# sensore-linea.net
KiCad netlist of a schematic drawn in EAGLE
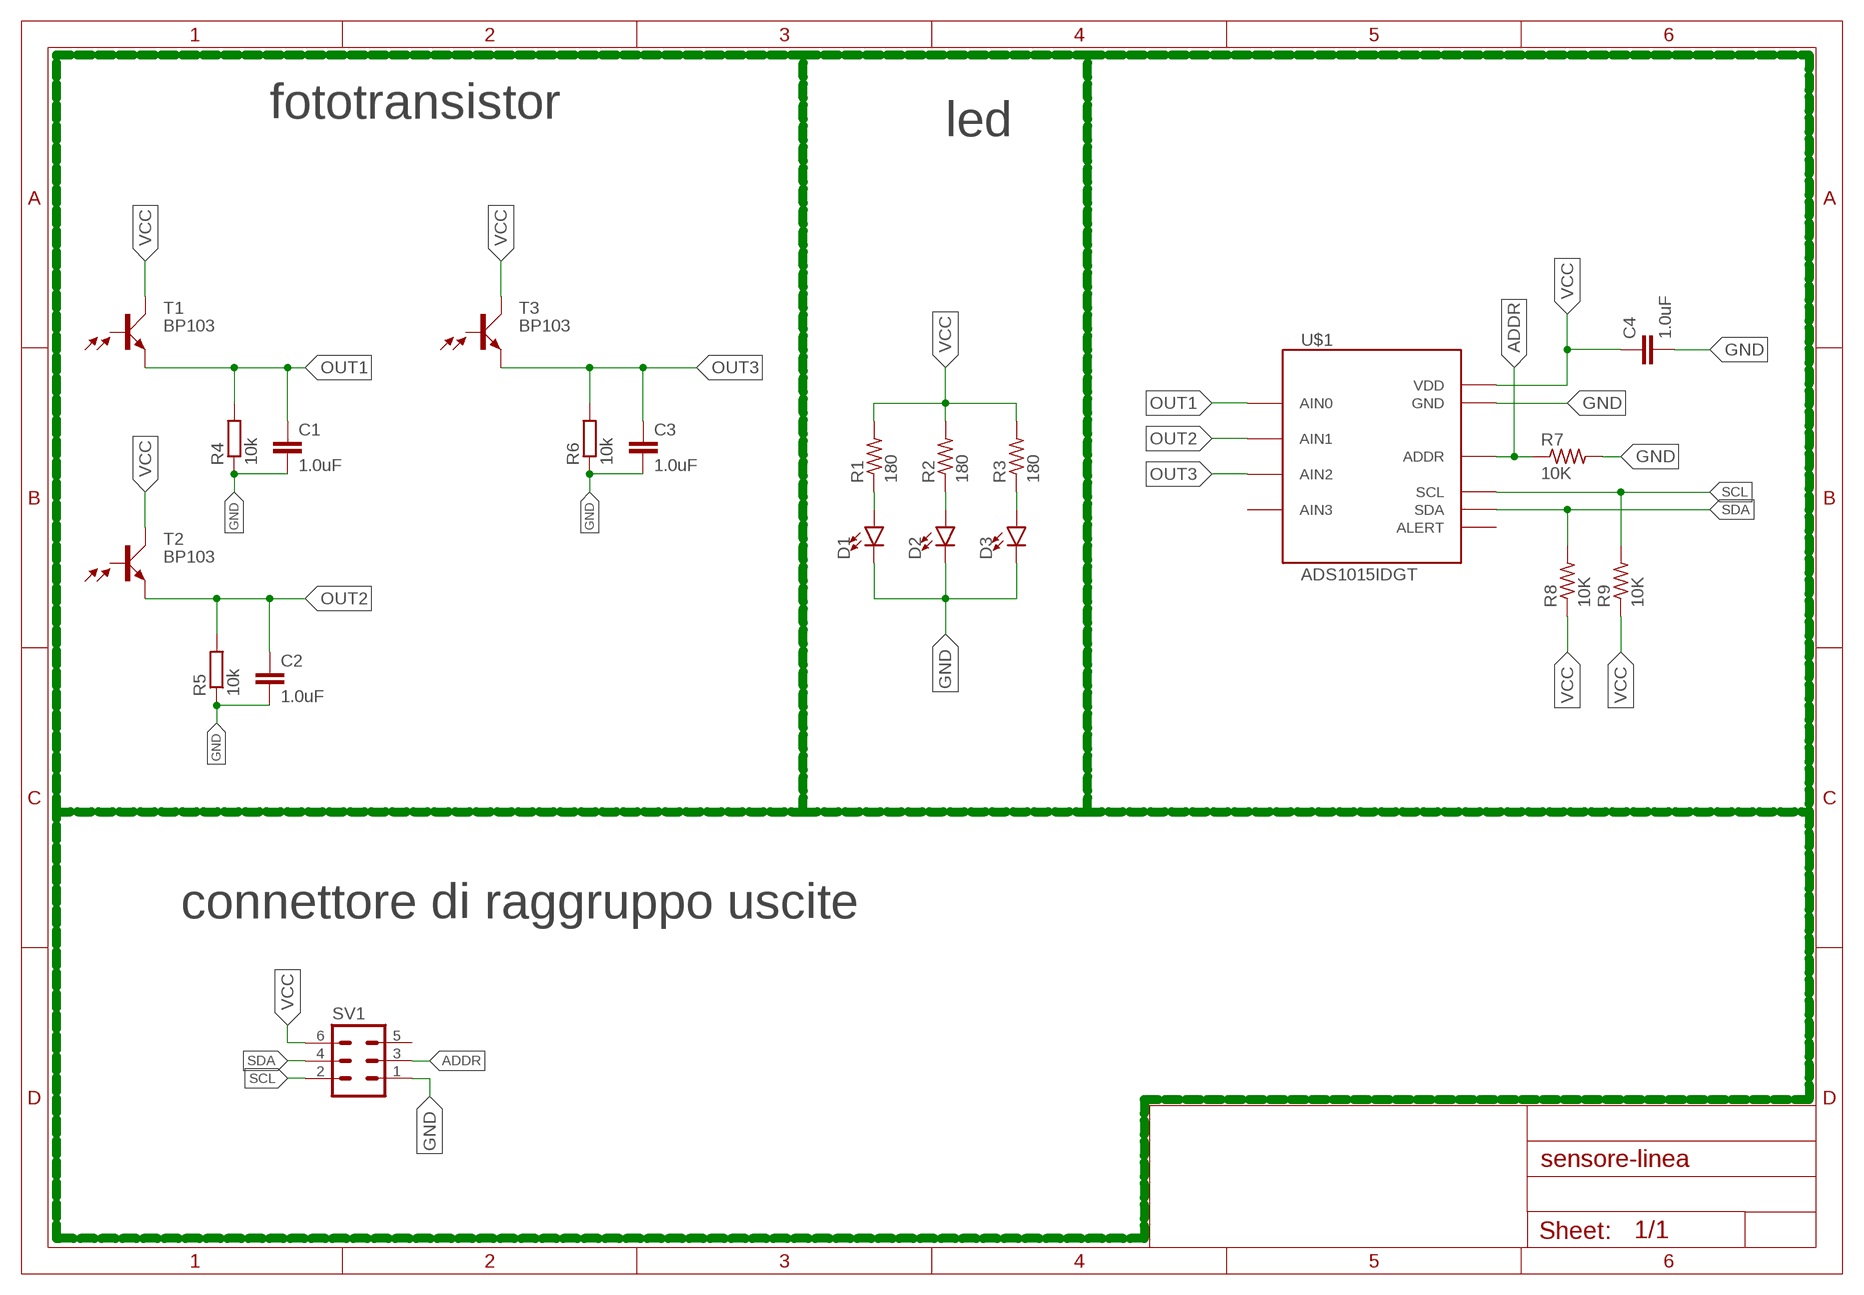
[diagram p0: schematic, sheet 1]

(export (version "E")
  (design (tool "Eeschema 10.0.6"))
  (components
    (comp (ref "C1")
      (value "1.0uF")
      (footprint "eagle-import:1206")
      (libsource (lib "eagle-import") (part "2.2UF-1206-50V-10%"))
    )
    (comp (ref "C2")
      (value "1.0uF")
      (footprint "eagle-import:1206")
      (libsource (lib "eagle-import") (part "2.2UF-1206-50V-10%"))
    )
    (comp (ref "C3")
      (value "1.0uF")
      (footprint "eagle-import:1206")
      (libsource (lib "eagle-import") (part "2.2UF-1206-50V-10%"))
    )
    (comp (ref "C4")
      (value "1.0uF")
      (footprint "eagle-import:0402")
      (libsource (lib "eagle-import") (part "1.0UF-0402-16V-10%"))
    )
    (comp (ref "D1")
      (value "LED3MM")
      (footprint "eagle-import:LED_3MM")
      (libsource (lib "eagle-import") (part "LED3MM"))
    )
    (comp (ref "D2")
      (value "LED3MM")
      (footprint "eagle-import:LED_3MM")
      (libsource (lib "eagle-import") (part "LED3MM"))
    )
    (comp (ref "D3")
      (value "LED3MM")
      (footprint "eagle-import:LED_3MM")
      (libsource (lib "eagle-import") (part "LED3MM"))
    )
    (comp (ref "R1")
      (value "180")
      (footprint "eagle-import:0204_7")
      (libsource (lib "eagle-import") (part "R-US_0204/7"))
    )
    (comp (ref "R2")
      (value "180")
      (footprint "eagle-import:0204_7")
      (libsource (lib "eagle-import") (part "R-US_0204/7"))
    )
    (comp (ref "R3")
      (value "180")
      (footprint "eagle-import:0204_7")
      (libsource (lib "eagle-import") (part "R-US_0204/7"))
    )
    (comp (ref "R4")
      (value "10k")
      (footprint "eagle-import:R1206")
      (libsource (lib "eagle-import") (part "R-EU_R1206"))
    )
    (comp (ref "R5")
      (value "10k")
      (footprint "eagle-import:R1206")
      (libsource (lib "eagle-import") (part "R-EU_R1206"))
    )
    (comp (ref "R6")
      (value "10k")
      (footprint "eagle-import:R1206")
      (libsource (lib "eagle-import") (part "R-EU_R1206"))
    )
    (comp (ref "R7")
      (value "10K")
      (footprint "eagle-import:0204_7")
      (libsource (lib "eagle-import") (part "resistor_348_R-US_0204/7"))
    )
    (comp (ref "R8")
      (value "10K")
      (footprint "eagle-import:0204_7")
      (libsource (lib "eagle-import") (part "resistor_348_R-US_0204/7"))
    )
    (comp (ref "R9")
      (value "10K")
      (footprint "eagle-import:0204_7")
      (libsource (lib "eagle-import") (part "resistor_348_R-US_0204/7"))
    )
    (comp (ref "SV1")
      (value "MA03-2")
      (footprint "eagle-import:MA03-2")
      (libsource (lib "eagle-import") (part "MA03-2"))
    )
    (comp (ref "T1")
      (value "BP103")
      (footprint "eagle-import:BP103")
      (libsource (lib "eagle-import") (part "BP103"))
    )
    (comp (ref "T2")
      (value "BP103")
      (footprint "eagle-import:BP103")
      (libsource (lib "eagle-import") (part "BP103"))
    )
    (comp (ref "T3")
      (value "BP103")
      (footprint "eagle-import:BP103")
      (libsource (lib "eagle-import") (part "BP103"))
    )
    (comp (ref "U$1")
      (value "ADS1015IDGT")
      (footprint "eagle-import:MSOP10_0.5")
      (libsource (lib "eagle-import") (part "ADS1015IDGT"))
    )
  )
  (nets
    (net (code "1") (name "ADDR") (class "Default")
      (node (ref "R7") (pin "1") (pinfunction "1_1") (pintype "passive"))
      (node (ref "SV1") (pin "3") (pinfunction "3_3") (pintype "passive"))
      (node (ref "U$1") (pin "1") (pinfunction "ADDR_1") (pintype "input"))
    )
    (net (code "2") (name "GND") (class "Default")
      (node (ref "C1") (pin "2") (pinfunction "2_2") (pintype "passive"))
      (node (ref "C2") (pin "2") (pinfunction "2_2") (pintype "passive"))
      (node (ref "C3") (pin "2") (pinfunction "2_2") (pintype "passive"))
      (node (ref "C4") (pin "2") (pinfunction "2_2") (pintype "passive"))
      (node (ref "D1") (pin "K") (pinfunction "C_K") (pintype "passive"))
      (node (ref "D2") (pin "K") (pinfunction "C_K") (pintype "passive"))
      (node (ref "D3") (pin "K") (pinfunction "C_K") (pintype "passive"))
      (node (ref "R4") (pin "1") (pinfunction "1_1") (pintype "passive"))
      (node (ref "R5") (pin "1") (pinfunction "1_1") (pintype "passive"))
      (node (ref "R6") (pin "1") (pinfunction "1_1") (pintype "passive"))
      (node (ref "R7") (pin "2") (pinfunction "2_2") (pintype "passive"))
      (node (ref "SV1") (pin "1") (pinfunction "1_1") (pintype "passive"))
      (node (ref "U$1") (pin "3") (pinfunction "GND_3") (pintype "power_in"))
    )
    (net (code "3") (name "Net-(D1-PadA)") (class "Default")
      (node (ref "D1") (pin "A") (pinfunction "A_A") (pintype "passive"))
      (node (ref "R1") (pin "1") (pinfunction "1_1") (pintype "passive"))
    )
    (net (code "4") (name "Net-(D2-PadA)") (class "Default")
      (node (ref "D2") (pin "A") (pinfunction "A_A") (pintype "passive"))
      (node (ref "R2") (pin "1") (pinfunction "1_1") (pintype "passive"))
    )
    (net (code "5") (name "Net-(D3-PadA)") (class "Default")
      (node (ref "D3") (pin "A") (pinfunction "A_A") (pintype "passive"))
      (node (ref "R3") (pin "1") (pinfunction "1_1") (pintype "passive"))
    )
    (net (code "6") (name "OUT1") (class "Default")
      (node (ref "C1") (pin "1") (pinfunction "1_1") (pintype "passive"))
      (node (ref "R4") (pin "2") (pinfunction "2_2") (pintype "passive"))
      (node (ref "T1") (pin "E") (pinfunction "E_E") (pintype "passive"))
      (node (ref "U$1") (pin "4") (pinfunction "AIN0_4") (pintype "input"))
    )
    (net (code "7") (name "OUT2") (class "Default")
      (node (ref "C2") (pin "1") (pinfunction "1_1") (pintype "passive"))
      (node (ref "R5") (pin "2") (pinfunction "2_2") (pintype "passive"))
      (node (ref "T2") (pin "E") (pinfunction "E_E") (pintype "passive"))
      (node (ref "U$1") (pin "5") (pinfunction "AIN1_5") (pintype "input"))
    )
    (net (code "8") (name "OUT3") (class "Default")
      (node (ref "C3") (pin "1") (pinfunction "1_1") (pintype "passive"))
      (node (ref "R6") (pin "2") (pinfunction "2_2") (pintype "passive"))
      (node (ref "T3") (pin "E") (pinfunction "E_E") (pintype "passive"))
      (node (ref "U$1") (pin "6") (pinfunction "AIN2_6") (pintype "input"))
    )
    (net (code "9") (name "SCL") (class "Default")
      (node (ref "R9") (pin "2") (pinfunction "2_2") (pintype "passive"))
      (node (ref "SV1") (pin "2") (pinfunction "2_2") (pintype "passive"))
      (node (ref "U$1") (pin "10") (pinfunction "SCL_10") (pintype "bidirectional"))
    )
    (net (code "10") (name "SDA") (class "Default")
      (node (ref "R8") (pin "2") (pinfunction "2_2") (pintype "passive"))
      (node (ref "SV1") (pin "4") (pinfunction "4_4") (pintype "passive"))
      (node (ref "U$1") (pin "9") (pinfunction "SDA_9") (pintype "bidirectional"))
    )
    (net (code "11") (name "VCC") (class "Default")
      (node (ref "C4") (pin "1") (pinfunction "1_1") (pintype "passive"))
      (node (ref "R1") (pin "2") (pinfunction "2_2") (pintype "passive"))
      (node (ref "R2") (pin "2") (pinfunction "2_2") (pintype "passive"))
      (node (ref "R3") (pin "2") (pinfunction "2_2") (pintype "passive"))
      (node (ref "R8") (pin "1") (pinfunction "1_1") (pintype "passive"))
      (node (ref "R9") (pin "1") (pinfunction "1_1") (pintype "passive"))
      (node (ref "SV1") (pin "6") (pinfunction "6_6") (pintype "passive"))
      (node (ref "T1") (pin "C") (pinfunction "C_C") (pintype "passive"))
      (node (ref "T2") (pin "C") (pinfunction "C_C") (pintype "passive"))
      (node (ref "T3") (pin "C") (pinfunction "C_C") (pintype "passive"))
      (node (ref "U$1") (pin "8") (pinfunction "VDD_8") (pintype "power_in"))
    )
    (net (code "12") (name "unconnected-(SV1-Pad5)") (class "Default")
      (node (ref "SV1") (pin "5") (pinfunction "5_5") (pintype "passive"))
    )
    (net (code "13") (name "unconnected-(T1-PadB)") (class "Default")
      (node (ref "T1") (pin "B") (pinfunction "B_B") (pintype "passive"))
    )
    (net (code "14") (name "unconnected-(T2-PadB)") (class "Default")
      (node (ref "T2") (pin "B") (pinfunction "B_B") (pintype "passive"))
    )
    (net (code "15") (name "unconnected-(T3-PadB)") (class "Default")
      (node (ref "T3") (pin "B") (pinfunction "B_B") (pintype "passive"))
    )
    (net (code "16") (name "unconnected-(U$1-AIN3-Pad7)") (class "Default")
      (node (ref "U$1") (pin "7") (pinfunction "AIN3_7") (pintype "input"))
    )
    (net (code "17") (name "unconnected-(U$1-ALERT-Pad2)") (class "Default")
      (node (ref "U$1") (pin "2") (pinfunction "ALERT_2") (pintype "output"))
    )
  )
)
